# Sheet5_1_5-2.net
KiCad netlist of a schematic drawn in Altium Designer
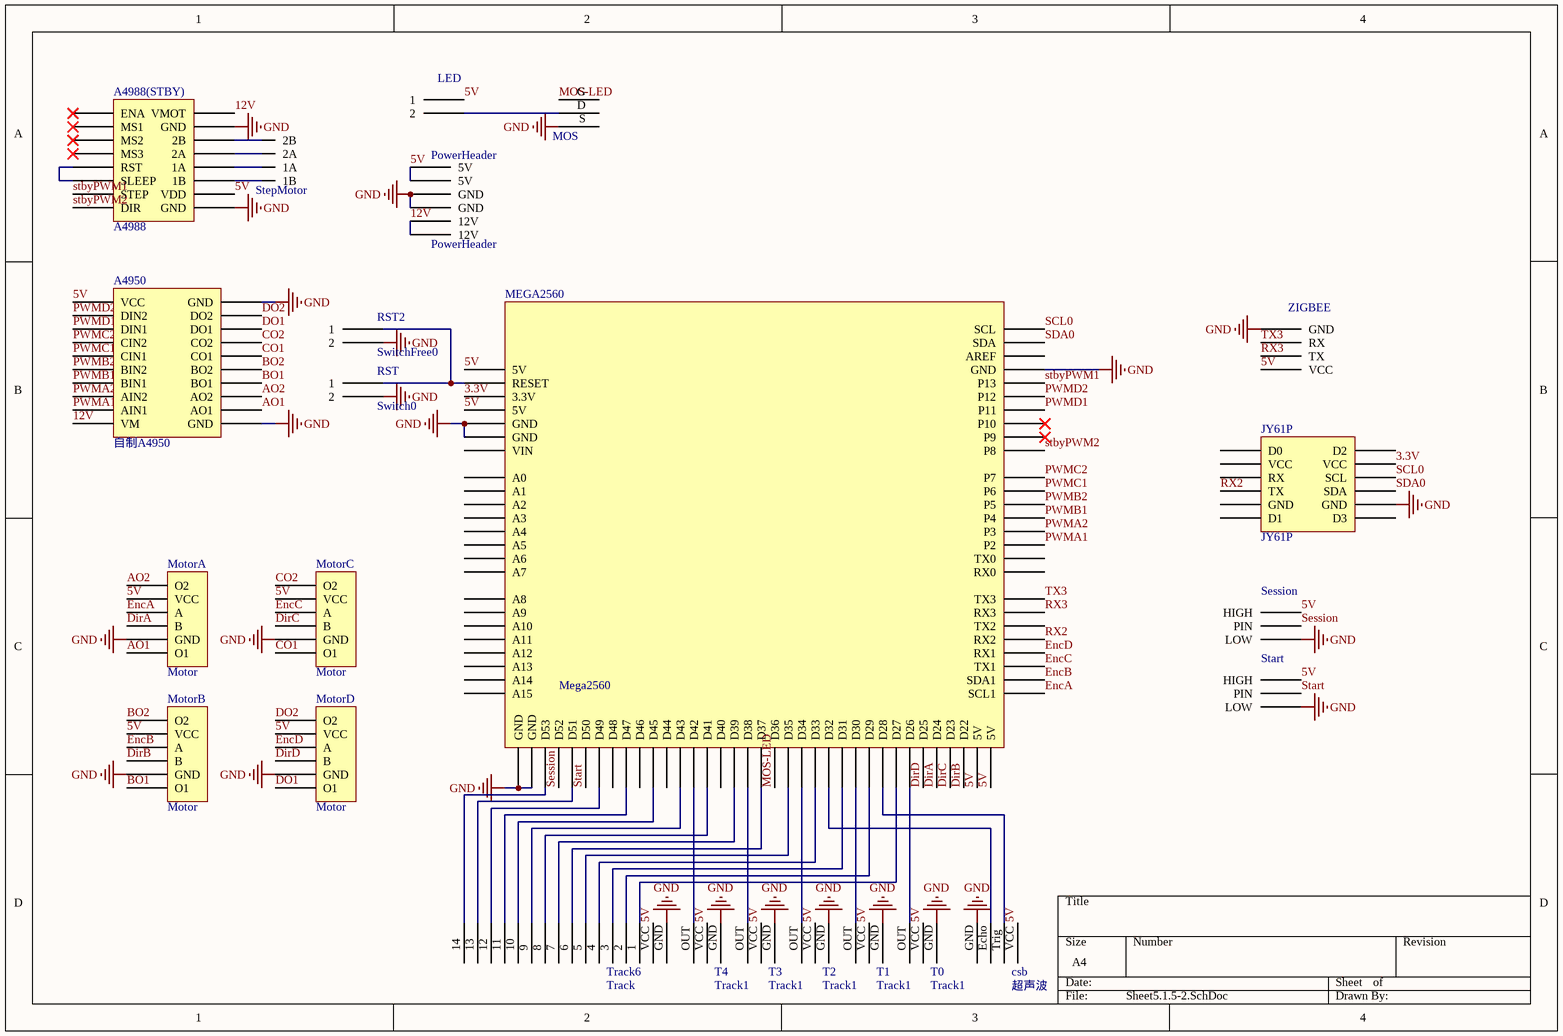
[diagram p0: Sheet5.1.5-2.SchDoc]

(export (version "E")
  (design (tool "Eeschema 10.0.6"))
  (components
    (comp (ref "A4950") (value "自制A4950") (footprint "自制A4950") (libsource (lib "Schlib1") (part "自制A4950")))
    (comp (ref "A4988(STBY)")
      (value "A4988")
      (footprint "A4988")
      (libsource (lib "Schlib5.2.0") (part "A4988"))
    )
    (comp (ref "csb") (value "超声波") (footprint "超声波") (libsource (lib "Schlib5.2.0") (part "超声波")))
    (comp (ref "JY61P") (value "JY61P") (footprint "JY61P") (libsource (lib "Schlib1") (part "JY61P")))
    (comp (ref "LED")
      (value "SwitchFree0")
      (footprint "SwitchFree")
      (libsource (lib "Schlib5.2.0") (part "SwitchFree0"))
    )
    (comp (ref "MEGA2560")
      (value "Mega2560")
      (footprint "MEGA2560")
      (libsource (lib "Schlib1") (part "Mega2560"))
    )
    (comp (ref "MOS") (value "MOS") (footprint "MOS") (libsource (lib "Schlib5.2.0") (part "MOS")))
    (comp (ref "MotorA") (value "Motor") (footprint "Motor") (libsource (lib "Schlib1") (part "Motor")))
    (comp (ref "MotorB") (value "Motor") (footprint "Motor") (libsource (lib "Schlib1") (part "Motor")))
    (comp (ref "MotorC") (value "Motor") (footprint "Motor") (libsource (lib "Schlib1") (part "Motor")))
    (comp (ref "MotorD") (value "Motor") (footprint "Motor") (libsource (lib "Schlib1") (part "Motor")))
    (comp (ref "PowerHeader")
      (value "PowerHeader")
      (footprint "PowerHeader")
      (libsource (lib "Schlib1") (part "PowerHeader"))
    )
    (comp (ref "RST")
      (value "Switch0")
      (footprint "Switch0")
      (libsource (lib "Schlib5.2.0") (part "Switch0"))
    )
    (comp (ref "RST2")
      (value "SwitchFree0")
      (footprint "SwitchFree")
      (libsource (lib "Schlib5.2.0") (part "SwitchFree0"))
    )
    (comp (ref "Session")
      (value "Switch3")
      (footprint "Switch3")
      (libsource (lib "Schlib5.2.0") (part "Switch3"))
    )
    (comp (ref "Start")
      (value "Switch3")
      (footprint "Switch3")
      (libsource (lib "Schlib5.2.0") (part "Switch3"))
    )
    (comp (ref "Step")
      (value "StepMotor")
      (footprint "StepMotor")
      (libsource (lib "Schlib5.2.0") (part "StepMotor"))
    )
    (comp (ref "T0") (value "Track1") (footprint "TRACK1") (libsource (lib "Schlib5.2.0") (part "Track1")))
    (comp (ref "T1") (value "Track1") (footprint "TRACK1") (libsource (lib "Schlib5.2.0") (part "Track1")))
    (comp (ref "T2") (value "Track1") (footprint "TRACK1") (libsource (lib "Schlib5.2.0") (part "Track1")))
    (comp (ref "T3") (value "Track1") (footprint "TRACK1") (libsource (lib "Schlib5.2.0") (part "Track1")))
    (comp (ref "T4") (value "Track1") (footprint "TRACK1") (libsource (lib "Schlib5.2.0") (part "Track1")))
    (comp (ref "Track6") (value "Track") (footprint "Track") (libsource (lib "Schlib5.2.0") (part "Track")))
    (comp (ref "ZIGBEE") (value "ZIGBEE") (footprint "ZIGBEE") (libsource (lib "Schlib1") (part "ZIGBEE")))
  )
  (nets
    (net (code "1") (name "/3.3V") (class "Default")
      (node (ref "JY61P") (pin "VCC") (pinfunction "VCC_VCC") (pintype "passive"))
      (node (ref "MEGA2560") (pin "3.3V") (pinfunction "3.3V_3.3V") (pintype "passive"))
    )
    (net (code "2") (name "/5V") (class "Default")
      (node (ref "A4950") (pin "VCC") (pinfunction "VCC_VCC") (pintype "passive"))
      (node (ref "A4988(STBY)") (pin "VDD") (pinfunction "VDD_VDD") (pintype "passive"))
      (node (ref "LED") (pin "1") (pinfunction "1_1") (pintype "passive"))
      (node (ref "MEGA2560") (pin "5V") (pinfunction "5V_5V") (pintype "passive"))
      (node (ref "MotorA") (pin "VCC") (pinfunction "VCC_VCC") (pintype "passive"))
      (node (ref "MotorB") (pin "VCC") (pinfunction "VCC_VCC") (pintype "passive"))
      (node (ref "MotorC") (pin "VCC") (pinfunction "VCC_VCC") (pintype "passive"))
      (node (ref "MotorD") (pin "VCC") (pinfunction "VCC_VCC") (pintype "passive"))
      (node (ref "PowerHeader") (pin "5V") (pinfunction "5V_5V") (pintype "passive"))
      (node (ref "Session") (pin "HIGH") (pinfunction "HIGH_HIGH") (pintype "passive"))
      (node (ref "Start") (pin "HIGH") (pinfunction "HIGH_HIGH") (pintype "passive"))
      (node (ref "T0") (pin "VCC") (pinfunction "VCC_VCC") (pintype "passive"))
      (node (ref "T1") (pin "VCC") (pinfunction "VCC_VCC") (pintype "passive"))
      (node (ref "T2") (pin "VCC") (pinfunction "VCC_VCC") (pintype "passive"))
      (node (ref "T3") (pin "VCC") (pinfunction "VCC_VCC") (pintype "passive"))
      (node (ref "T4") (pin "VCC") (pinfunction "VCC_VCC") (pintype "passive"))
      (node (ref "Track6") (pin "VCC") (pinfunction "VCC_VCC") (pintype "passive"))
      (node (ref "ZIGBEE") (pin "VCC") (pinfunction "VCC_VCC") (pintype "passive"))
      (node (ref "csb") (pin "VCC") (pinfunction "VCC_VCC") (pintype "passive"))
    )
    (net (code "3") (name "/12V") (class "Default")
      (node (ref "A4950") (pin "VM") (pinfunction "VM_VM") (pintype "passive"))
      (node (ref "A4988(STBY)") (pin "VMOT") (pinfunction "VMOT_VMOT") (pintype "passive"))
      (node (ref "PowerHeader") (pin "12V") (pinfunction "12V_12V") (pintype "passive"))
    )
    (net (code "4") (name "/AO1") (class "Default")
      (node (ref "A4950") (pin "AO1") (pinfunction "AO1_AO1") (pintype "passive"))
      (node (ref "MotorA") (pin "O1") (pinfunction "O1_O1") (pintype "passive"))
    )
    (net (code "5") (name "/AO2") (class "Default")
      (node (ref "A4950") (pin "AO2") (pinfunction "AO2_AO2") (pintype "passive"))
      (node (ref "MotorA") (pin "O2") (pinfunction "O2_O2") (pintype "passive"))
    )
    (net (code "6") (name "/BO1") (class "Default")
      (node (ref "A4950") (pin "BO1") (pinfunction "BO1_BO1") (pintype "passive"))
      (node (ref "MotorB") (pin "O1") (pinfunction "O1_O1") (pintype "passive"))
    )
    (net (code "7") (name "/BO2") (class "Default")
      (node (ref "A4950") (pin "BO2") (pinfunction "BO2_BO2") (pintype "passive"))
      (node (ref "MotorB") (pin "O2") (pinfunction "O2_O2") (pintype "passive"))
    )
    (net (code "8") (name "/CO1") (class "Default")
      (node (ref "A4950") (pin "CO1") (pinfunction "CO1_CO1") (pintype "passive"))
      (node (ref "MotorC") (pin "O1") (pinfunction "O1_O1") (pintype "passive"))
    )
    (net (code "9") (name "/CO2") (class "Default")
      (node (ref "A4950") (pin "CO2") (pinfunction "CO2_CO2") (pintype "passive"))
      (node (ref "MotorC") (pin "O2") (pinfunction "O2_O2") (pintype "passive"))
    )
    (net (code "10") (name "/DO1") (class "Default")
      (node (ref "A4950") (pin "DO1") (pinfunction "DO1_DO1") (pintype "passive"))
      (node (ref "MotorD") (pin "O1") (pinfunction "O1_O1") (pintype "passive"))
    )
    (net (code "11") (name "/DO2") (class "Default")
      (node (ref "A4950") (pin "DO2") (pinfunction "DO2_DO2") (pintype "passive"))
      (node (ref "MotorD") (pin "O2") (pinfunction "O2_O2") (pintype "passive"))
    )
    (net (code "12") (name "/DirA") (class "Default")
      (node (ref "MEGA2560") (pin "D24") (pinfunction "D24_D24") (pintype "passive"))
      (node (ref "MotorA") (pin "B") (pinfunction "B_B") (pintype "passive"))
    )
    (net (code "13") (name "/DirB") (class "Default")
      (node (ref "MEGA2560") (pin "D22") (pinfunction "D22_D22") (pintype "passive"))
      (node (ref "MotorB") (pin "B") (pinfunction "B_B") (pintype "passive"))
    )
    (net (code "14") (name "/DirC") (class "Default")
      (node (ref "MEGA2560") (pin "D23") (pinfunction "D23_D23") (pintype "passive"))
      (node (ref "MotorC") (pin "B") (pinfunction "B_B") (pintype "passive"))
    )
    (net (code "15") (name "/DirD") (class "Default")
      (node (ref "MEGA2560") (pin "D25") (pinfunction "D25_D25") (pintype "passive"))
      (node (ref "MotorD") (pin "B") (pinfunction "B_B") (pintype "passive"))
    )
    (net (code "16") (name "/EncA") (class "Default")
      (node (ref "MEGA2560") (pin "SCL1") (pinfunction "SCL1_SCL1") (pintype "passive"))
      (node (ref "MotorA") (pin "A") (pinfunction "A_A") (pintype "passive"))
    )
    (net (code "17") (name "/EncB") (class "Default")
      (node (ref "MEGA2560") (pin "SDA1") (pinfunction "SDA1_SDA1") (pintype "passive"))
      (node (ref "MotorB") (pin "A") (pinfunction "A_A") (pintype "passive"))
    )
    (net (code "18") (name "/EncC") (class "Default")
      (node (ref "MEGA2560") (pin "TX1") (pinfunction "TX1_TX1") (pintype "passive"))
      (node (ref "MotorC") (pin "A") (pinfunction "A_A") (pintype "passive"))
    )
    (net (code "19") (name "/EncD") (class "Default")
      (node (ref "MEGA2560") (pin "RX1") (pinfunction "RX1_RX1") (pintype "passive"))
      (node (ref "MotorD") (pin "A") (pinfunction "A_A") (pintype "passive"))
    )
    (net (code "20") (name "/MOS-LED") (class "Default")
      (node (ref "MEGA2560") (pin "D36") (pinfunction "D36_D36") (pintype "passive"))
      (node (ref "MOS") (pin "G") (pinfunction "G_G") (pintype "passive"))
    )
    (net (code "21") (name "/PWMA1") (class "Default")
      (node (ref "A4950") (pin "AIN1") (pinfunction "AIN1_AIN1") (pintype "passive"))
      (node (ref "MEGA2560") (pin "P2") (pinfunction "P2_P2") (pintype "passive"))
    )
    (net (code "22") (name "/PWMA2") (class "Default")
      (node (ref "A4950") (pin "AIN2") (pinfunction "AIN2_AIN2") (pintype "passive"))
      (node (ref "MEGA2560") (pin "P3") (pinfunction "P3_P3") (pintype "passive"))
    )
    (net (code "23") (name "/PWMB1") (class "Default")
      (node (ref "A4950") (pin "BIN1") (pinfunction "BIN1_BIN1") (pintype "passive"))
      (node (ref "MEGA2560") (pin "P4") (pinfunction "P4_P4") (pintype "passive"))
    )
    (net (code "24") (name "/PWMB2") (class "Default")
      (node (ref "A4950") (pin "BIN2") (pinfunction "BIN2_BIN2") (pintype "passive"))
      (node (ref "MEGA2560") (pin "P5") (pinfunction "P5_P5") (pintype "passive"))
    )
    (net (code "25") (name "/PWMC1") (class "Default")
      (node (ref "A4950") (pin "CIN1") (pinfunction "CIN1_CIN1") (pintype "passive"))
      (node (ref "MEGA2560") (pin "P6") (pinfunction "P6_P6") (pintype "passive"))
    )
    (net (code "26") (name "/PWMC2") (class "Default")
      (node (ref "A4950") (pin "CIN2") (pinfunction "CIN2_CIN2") (pintype "passive"))
      (node (ref "MEGA2560") (pin "P7") (pinfunction "P7_P7") (pintype "passive"))
    )
    (net (code "27") (name "/PWMD1") (class "Default")
      (node (ref "A4950") (pin "DIN1") (pinfunction "DIN1_DIN1") (pintype "passive"))
      (node (ref "MEGA2560") (pin "P11") (pinfunction "P11_P11") (pintype "passive"))
    )
    (net (code "28") (name "/PWMD2") (class "Default")
      (node (ref "A4950") (pin "DIN2") (pinfunction "DIN2_DIN2") (pintype "passive"))
      (node (ref "MEGA2560") (pin "P12") (pinfunction "P12_P12") (pintype "passive"))
    )
    (net (code "29") (name "/RX2") (class "Default")
      (node (ref "JY61P") (pin "TX") (pinfunction "TX_TX") (pintype "passive"))
      (node (ref "MEGA2560") (pin "RX2") (pinfunction "RX2_RX2") (pintype "passive"))
    )
    (net (code "30") (name "/RX3") (class "Default")
      (node (ref "MEGA2560") (pin "RX3") (pinfunction "RX3_RX3") (pintype "passive"))
      (node (ref "ZIGBEE") (pin "TX") (pinfunction "TX_TX") (pintype "passive"))
    )
    (net (code "31") (name "/SCL0") (class "Default")
      (node (ref "JY61P") (pin "SCL") (pinfunction "SCL_SCL") (pintype "passive"))
      (node (ref "MEGA2560") (pin "SCL") (pinfunction "SCL_SCL") (pintype "passive"))
    )
    (net (code "32") (name "/SDA0") (class "Default")
      (node (ref "JY61P") (pin "SDA") (pinfunction "SDA_SDA") (pintype "passive"))
      (node (ref "MEGA2560") (pin "SDA") (pinfunction "SDA_SDA") (pintype "passive"))
    )
    (net (code "33") (name "/Session") (class "Default")
      (node (ref "MEGA2560") (pin "D52") (pinfunction "D52_D52") (pintype "passive"))
      (node (ref "Session") (pin "PIN") (pinfunction "PIN_PIN") (pintype "passive"))
    )
    (net (code "34") (name "/Start") (class "Default")
      (node (ref "MEGA2560") (pin "D50") (pinfunction "D50_D50") (pintype "passive"))
      (node (ref "Start") (pin "PIN") (pinfunction "PIN_PIN") (pintype "passive"))
    )
    (net (code "35") (name "/TX3") (class "Default")
      (node (ref "MEGA2560") (pin "TX3") (pinfunction "TX3_TX3") (pintype "passive"))
      (node (ref "ZIGBEE") (pin "RX") (pinfunction "RX_RX") (pintype "passive"))
    )
    (net (code "36") (name "/stbyPWM1") (class "Default")
      (node (ref "A4988(STBY)") (pin "STEP") (pinfunction "STEP_STEP") (pintype "passive"))
      (node (ref "MEGA2560") (pin "P13") (pinfunction "P13_P13") (pintype "passive"))
    )
    (net (code "37") (name "/stbyPWM2") (class "Default")
      (node (ref "A4988(STBY)") (pin "DIR") (pinfunction "DIR_DIR") (pintype "passive"))
      (node (ref "MEGA2560") (pin "P8") (pinfunction "P8_P8") (pintype "passive"))
    )
    (net (code "38") (name "GND") (class "Default")
      (node (ref "A4950") (pin "GND") (pinfunction "GND_GND") (pintype "passive"))
      (node (ref "A4988(STBY)") (pin "GND") (pinfunction "GND_GND") (pintype "passive"))
      (node (ref "JY61P") (pin "GND") (pinfunction "GND_GND") (pintype "passive"))
      (node (ref "MEGA2560") (pin "GND") (pinfunction "GND_GND") (pintype "passive"))
      (node (ref "MOS") (pin "S") (pinfunction "S_S") (pintype "passive"))
      (node (ref "MotorA") (pin "GND") (pinfunction "GND_GND") (pintype "passive"))
      (node (ref "MotorB") (pin "GND") (pinfunction "GND_GND") (pintype "passive"))
      (node (ref "MotorC") (pin "GND") (pinfunction "GND_GND") (pintype "passive"))
      (node (ref "MotorD") (pin "GND") (pinfunction "GND_GND") (pintype "passive"))
      (node (ref "PowerHeader") (pin "GND") (pinfunction "GND_GND") (pintype "passive"))
      (node (ref "RST") (pin "2") (pinfunction "2_2") (pintype "passive"))
      (node (ref "RST2") (pin "2") (pinfunction "2_2") (pintype "passive"))
      (node (ref "Session") (pin "LOW") (pinfunction "LOW_LOW") (pintype "passive"))
      (node (ref "Start") (pin "LOW") (pinfunction "LOW_LOW") (pintype "passive"))
      (node (ref "T0") (pin "GND") (pinfunction "GND_GND") (pintype "passive"))
      (node (ref "T1") (pin "GND") (pinfunction "GND_GND") (pintype "passive"))
      (node (ref "T2") (pin "GND") (pinfunction "GND_GND") (pintype "passive"))
      (node (ref "T3") (pin "GND") (pinfunction "GND_GND") (pintype "passive"))
      (node (ref "T4") (pin "GND") (pinfunction "GND_GND") (pintype "passive"))
      (node (ref "Track6") (pin "GND") (pinfunction "GND_GND") (pintype "passive"))
      (node (ref "ZIGBEE") (pin "GND") (pinfunction "GND_GND") (pintype "passive"))
      (node (ref "csb") (pin "GND") (pinfunction "GND_GND") (pintype "passive"))
    )
    (net (code "39") (name "Net-(A4988(STBY)-Pad1A)") (class "Default")
      (node (ref "A4988(STBY)") (pin "1A") (pinfunction "1A_1A") (pintype "passive"))
      (node (ref "Step") (pin "1A") (pinfunction "1A_1A") (pintype "passive"))
    )
    (net (code "40") (name "Net-(A4988(STBY)-Pad1B)") (class "Default")
      (node (ref "A4988(STBY)") (pin "1B") (pinfunction "1B_1B") (pintype "passive"))
      (node (ref "Step") (pin "1B") (pinfunction "1B_1B") (pintype "passive"))
    )
    (net (code "41") (name "Net-(A4988(STBY)-Pad2A)") (class "Default")
      (node (ref "A4988(STBY)") (pin "2A") (pinfunction "2A_2A") (pintype "passive"))
      (node (ref "Step") (pin "2A") (pinfunction "2A_2A") (pintype "passive"))
    )
    (net (code "42") (name "Net-(A4988(STBY)-Pad2B)") (class "Default")
      (node (ref "A4988(STBY)") (pin "2B") (pinfunction "2B_2B") (pintype "passive"))
      (node (ref "Step") (pin "2B") (pinfunction "2B_2B") (pintype "passive"))
    )
    (net (code "43") (name "Net-(A4988(STBY)-PadRST)") (class "Default")
      (node (ref "A4988(STBY)") (pin "RST") (pinfunction "RST_RST") (pintype "passive"))
      (node (ref "A4988(STBY)") (pin "SLEEP") (pinfunction "SLEEP_SLEEP") (pintype "passive"))
    )
    (net (code "44") (name "Net-(LED-Pad2)") (class "Default")
      (node (ref "LED") (pin "2") (pinfunction "2_2") (pintype "passive"))
      (node (ref "MOS") (pin "D") (pinfunction "D_D") (pintype "passive"))
    )
    (net (code "45") (name "Net-(MEGA2560-PadD26)") (class "Default")
      (node (ref "MEGA2560") (pin "D26") (pinfunction "D26_D26") (pintype "passive"))
      (node (ref "T0") (pin "OUT") (pinfunction "OUT_OUT") (pintype "passive"))
    )
    (net (code "46") (name "Net-(MEGA2560-PadD27)") (class "Default")
      (node (ref "MEGA2560") (pin "D27") (pinfunction "D27_D27") (pintype "passive"))
      (node (ref "Track6") (pin "1") (pinfunction "1_1") (pintype "passive"))
    )
    (net (code "47") (name "Net-(MEGA2560-PadD28)") (class "Default")
      (node (ref "MEGA2560") (pin "D28") (pinfunction "D28_D28") (pintype "passive"))
      (node (ref "csb") (pin "Trig") (pinfunction "Trig_Trig") (pintype "passive"))
    )
    (net (code "48") (name "Net-(MEGA2560-PadD29)") (class "Default")
      (node (ref "MEGA2560") (pin "D29") (pinfunction "D29_D29") (pintype "passive"))
      (node (ref "Track6") (pin "2") (pinfunction "2_2") (pintype "passive"))
    )
    (net (code "49") (name "Net-(MEGA2560-PadD30)") (class "Default")
      (node (ref "MEGA2560") (pin "D30") (pinfunction "D30_D30") (pintype "passive"))
      (node (ref "T1") (pin "OUT") (pinfunction "OUT_OUT") (pintype "passive"))
    )
    (net (code "50") (name "Net-(MEGA2560-PadD31)") (class "Default")
      (node (ref "MEGA2560") (pin "D31") (pinfunction "D31_D31") (pintype "passive"))
      (node (ref "Track6") (pin "3") (pinfunction "3_3") (pintype "passive"))
    )
    (net (code "51") (name "Net-(MEGA2560-PadD32)") (class "Default")
      (node (ref "MEGA2560") (pin "D32") (pinfunction "D32_D32") (pintype "passive"))
      (node (ref "csb") (pin "Echo") (pinfunction "Echo_Echo") (pintype "passive"))
    )
    (net (code "52") (name "Net-(MEGA2560-PadD33)") (class "Default")
      (node (ref "MEGA2560") (pin "D33") (pinfunction "D33_D33") (pintype "passive"))
      (node (ref "Track6") (pin "4") (pinfunction "4_4") (pintype "passive"))
    )
    (net (code "53") (name "Net-(MEGA2560-PadD34)") (class "Default")
      (node (ref "MEGA2560") (pin "D34") (pinfunction "D34_D34") (pintype "passive"))
      (node (ref "T2") (pin "OUT") (pinfunction "OUT_OUT") (pintype "passive"))
    )
    (net (code "54") (name "Net-(MEGA2560-PadD35)") (class "Default")
      (node (ref "MEGA2560") (pin "D35") (pinfunction "D35_D35") (pintype "passive"))
      (node (ref "Track6") (pin "5") (pinfunction "5_5") (pintype "passive"))
    )
    (net (code "55") (name "Net-(MEGA2560-PadD37)") (class "Default")
      (node (ref "MEGA2560") (pin "D37") (pinfunction "D37_D37") (pintype "passive"))
      (node (ref "Track6") (pin "6") (pinfunction "6_6") (pintype "passive"))
    )
    (net (code "56") (name "Net-(MEGA2560-PadD38)") (class "Default")
      (node (ref "MEGA2560") (pin "D38") (pinfunction "D38_D38") (pintype "passive"))
      (node (ref "T3") (pin "OUT") (pinfunction "OUT_OUT") (pintype "passive"))
    )
    (net (code "57") (name "Net-(MEGA2560-PadD39)") (class "Default")
      (node (ref "MEGA2560") (pin "D39") (pinfunction "D39_D39") (pintype "passive"))
      (node (ref "Track6") (pin "7") (pinfunction "7_7") (pintype "passive"))
    )
    (net (code "58") (name "Net-(MEGA2560-PadD41)") (class "Default")
      (node (ref "MEGA2560") (pin "D41") (pinfunction "D41_D41") (pintype "passive"))
      (node (ref "Track6") (pin "8") (pinfunction "8_8") (pintype "passive"))
    )
    (net (code "59") (name "Net-(MEGA2560-PadD42)") (class "Default")
      (node (ref "MEGA2560") (pin "D42") (pinfunction "D42_D42") (pintype "passive"))
      (node (ref "T4") (pin "OUT") (pinfunction "OUT_OUT") (pintype "passive"))
    )
    (net (code "60") (name "Net-(MEGA2560-PadD43)") (class "Default")
      (node (ref "MEGA2560") (pin "D43") (pinfunction "D43_D43") (pintype "passive"))
      (node (ref "Track6") (pin "9") (pinfunction "9_9") (pintype "passive"))
    )
    (net (code "61") (name "Net-(MEGA2560-PadD45)") (class "Default")
      (node (ref "MEGA2560") (pin "D45") (pinfunction "D45_D45") (pintype "passive"))
      (node (ref "Track6") (pin "10") (pinfunction "10_10") (pintype "passive"))
    )
    (net (code "62") (name "Net-(MEGA2560-PadD47)") (class "Default")
      (node (ref "MEGA2560") (pin "D47") (pinfunction "D47_D47") (pintype "passive"))
      (node (ref "Track6") (pin "11") (pinfunction "11_11") (pintype "passive"))
    )
    (net (code "63") (name "Net-(MEGA2560-PadD49)") (class "Default")
      (node (ref "MEGA2560") (pin "D49") (pinfunction "D49_D49") (pintype "passive"))
      (node (ref "Track6") (pin "12") (pinfunction "12_12") (pintype "passive"))
    )
    (net (code "64") (name "Net-(MEGA2560-PadD51)") (class "Default")
      (node (ref "MEGA2560") (pin "D51") (pinfunction "D51_D51") (pintype "passive"))
      (node (ref "Track6") (pin "13") (pinfunction "13_13") (pintype "passive"))
    )
    (net (code "65") (name "Net-(MEGA2560-PadD53)") (class "Default")
      (node (ref "MEGA2560") (pin "D53") (pinfunction "D53_D53") (pintype "passive"))
      (node (ref "Track6") (pin "14") (pinfunction "14_14") (pintype "passive"))
    )
    (net (code "66") (name "Net-(MEGA2560-PadRESET)") (class "Default")
      (node (ref "MEGA2560") (pin "RESET") (pinfunction "RESET_RESET") (pintype "passive"))
      (node (ref "RST") (pin "1") (pinfunction "1_1") (pintype "passive"))
      (node (ref "RST2") (pin "1") (pinfunction "1_1") (pintype "passive"))
    )
    (net (code "67") (name "unconnected-(A4988(STBY)-PadENA)") (class "Default")
      (node (ref "A4988(STBY)") (pin "ENA") (pinfunction "ENA_ENA") (pintype "passive+no_connect"))
    )
    (net (code "68") (name "unconnected-(A4988(STBY)-PadMS1)") (class "Default")
      (node (ref "A4988(STBY)") (pin "MS1") (pinfunction "MS1_MS1") (pintype "passive+no_connect"))
    )
    (net (code "69") (name "unconnected-(A4988(STBY)-PadMS2)") (class "Default")
      (node (ref "A4988(STBY)") (pin "MS2") (pinfunction "MS2_MS2") (pintype "passive+no_connect"))
    )
    (net (code "70") (name "unconnected-(A4988(STBY)-PadMS3)") (class "Default")
      (node (ref "A4988(STBY)") (pin "MS3") (pinfunction "MS3_MS3") (pintype "passive+no_connect"))
    )
    (net (code "71") (name "unconnected-(JY61P-PadD0)") (class "Default")
      (node (ref "JY61P") (pin "D0") (pinfunction "D0_D0") (pintype "passive"))
    )
    (net (code "72") (name "unconnected-(JY61P-PadD1)") (class "Default")
      (node (ref "JY61P") (pin "D1") (pinfunction "D1_D1") (pintype "passive"))
    )
    (net (code "73") (name "unconnected-(JY61P-PadD2)") (class "Default")
      (node (ref "JY61P") (pin "D2") (pinfunction "D2_D2") (pintype "passive"))
    )
    (net (code "74") (name "unconnected-(JY61P-PadD3)") (class "Default")
      (node (ref "JY61P") (pin "D3") (pinfunction "D3_D3") (pintype "passive"))
    )
    (net (code "75") (name "unconnected-(JY61P-PadGND)") (class "Default")
      (node (ref "JY61P") (pin "GND") (pinfunction "GND_GND") (pintype "passive"))
    )
    (net (code "76") (name "unconnected-(JY61P-PadRX)") (class "Default")
      (node (ref "JY61P") (pin "RX") (pinfunction "RX_RX") (pintype "passive"))
    )
    (net (code "77") (name "unconnected-(JY61P-PadVCC)") (class "Default")
      (node (ref "JY61P") (pin "VCC") (pinfunction "VCC_VCC") (pintype "passive"))
    )
    (net (code "78") (name "unconnected-(MEGA2560-PadA0)") (class "Default")
      (node (ref "MEGA2560") (pin "A0") (pinfunction "A0_A0") (pintype "passive"))
    )
    (net (code "79") (name "unconnected-(MEGA2560-PadA1)") (class "Default")
      (node (ref "MEGA2560") (pin "A1") (pinfunction "A1_A1") (pintype "passive"))
    )
    (net (code "80") (name "unconnected-(MEGA2560-PadA2)") (class "Default")
      (node (ref "MEGA2560") (pin "A2") (pinfunction "A2_A2") (pintype "passive"))
    )
    (net (code "81") (name "unconnected-(MEGA2560-PadA3)") (class "Default")
      (node (ref "MEGA2560") (pin "A3") (pinfunction "A3_A3") (pintype "passive"))
    )
    (net (code "82") (name "unconnected-(MEGA2560-PadA4)") (class "Default")
      (node (ref "MEGA2560") (pin "A4") (pinfunction "A4_A4") (pintype "passive"))
    )
    (net (code "83") (name "unconnected-(MEGA2560-PadA5)") (class "Default")
      (node (ref "MEGA2560") (pin "A5") (pinfunction "A5_A5") (pintype "passive"))
    )
    (net (code "84") (name "unconnected-(MEGA2560-PadA6)") (class "Default")
      (node (ref "MEGA2560") (pin "A6") (pinfunction "A6_A6") (pintype "passive"))
    )
    (net (code "85") (name "unconnected-(MEGA2560-PadA7)") (class "Default")
      (node (ref "MEGA2560") (pin "A7") (pinfunction "A7_A7") (pintype "passive"))
    )
    (net (code "86") (name "unconnected-(MEGA2560-PadA8)") (class "Default")
      (node (ref "MEGA2560") (pin "A8") (pinfunction "A8_A8") (pintype "passive"))
    )
    (net (code "87") (name "unconnected-(MEGA2560-PadA9)") (class "Default")
      (node (ref "MEGA2560") (pin "A9") (pinfunction "A9_A9") (pintype "passive"))
    )
    (net (code "88") (name "unconnected-(MEGA2560-PadA10)") (class "Default")
      (node (ref "MEGA2560") (pin "A10") (pinfunction "A10_A10") (pintype "passive"))
    )
    (net (code "89") (name "unconnected-(MEGA2560-PadA11)") (class "Default")
      (node (ref "MEGA2560") (pin "A11") (pinfunction "A11_A11") (pintype "passive"))
    )
    (net (code "90") (name "unconnected-(MEGA2560-PadA12)") (class "Default")
      (node (ref "MEGA2560") (pin "A12") (pinfunction "A12_A12") (pintype "passive"))
    )
    (net (code "91") (name "unconnected-(MEGA2560-PadA13)") (class "Default")
      (node (ref "MEGA2560") (pin "A13") (pinfunction "A13_A13") (pintype "passive"))
    )
    (net (code "92") (name "unconnected-(MEGA2560-PadA14)") (class "Default")
      (node (ref "MEGA2560") (pin "A14") (pinfunction "A14_A14") (pintype "passive"))
    )
    (net (code "93") (name "unconnected-(MEGA2560-PadA15)") (class "Default")
      (node (ref "MEGA2560") (pin "A15") (pinfunction "A15_A15") (pintype "passive"))
    )
    (net (code "94") (name "unconnected-(MEGA2560-PadAREF)") (class "Default")
      (node (ref "MEGA2560") (pin "AREF") (pinfunction "AREF_AREF") (pintype "passive"))
    )
    (net (code "95") (name "unconnected-(MEGA2560-PadD40)") (class "Default")
      (node (ref "MEGA2560") (pin "D40") (pinfunction "D40_D40") (pintype "passive"))
    )
    (net (code "96") (name "unconnected-(MEGA2560-PadD44)") (class "Default")
      (node (ref "MEGA2560") (pin "D44") (pinfunction "D44_D44") (pintype "passive"))
    )
    (net (code "97") (name "unconnected-(MEGA2560-PadD46)") (class "Default")
      (node (ref "MEGA2560") (pin "D46") (pinfunction "D46_D46") (pintype "passive"))
    )
    (net (code "98") (name "unconnected-(MEGA2560-PadD48)") (class "Default")
      (node (ref "MEGA2560") (pin "D48") (pinfunction "D48_D48") (pintype "passive"))
    )
    (net (code "99") (name "unconnected-(MEGA2560-PadP9)") (class "Default")
      (node (ref "MEGA2560") (pin "P9") (pinfunction "P9_P9") (pintype "passive+no_connect"))
    )
    (net (code "100") (name "unconnected-(MEGA2560-PadP10)") (class "Default")
      (node (ref "MEGA2560") (pin "P10") (pinfunction "P10_P10") (pintype "passive+no_connect"))
    )
    (net (code "101") (name "unconnected-(MEGA2560-PadRX0)") (class "Default")
      (node (ref "MEGA2560") (pin "RX0") (pinfunction "RX0_RX0") (pintype "passive"))
    )
    (net (code "102") (name "unconnected-(MEGA2560-PadTX0)") (class "Default")
      (node (ref "MEGA2560") (pin "TX0") (pinfunction "TX0_TX0") (pintype "passive"))
    )
    (net (code "103") (name "unconnected-(MEGA2560-PadTX2)") (class "Default")
      (node (ref "MEGA2560") (pin "TX2") (pinfunction "TX2_TX2") (pintype "passive"))
    )
    (net (code "104") (name "unconnected-(MEGA2560-PadVIN)") (class "Default")
      (node (ref "MEGA2560") (pin "VIN") (pinfunction "VIN_VIN") (pintype "passive"))
    )
  )
)
